# FOLLOWER_DIVIDER.net
KiCad netlist of a schematic drawn in Altium Designer
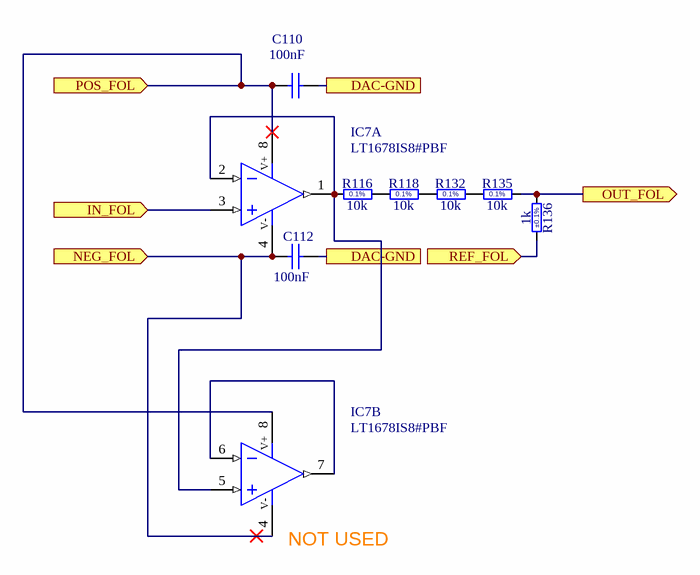
[diagram p0: FOLLOWER_DIVIDER.SchDoc]

(export (version "E")
  (design (tool "Eeschema 10.0.6"))
  (components
    (comp (ref "C110")
      (value "100nF")
      (footprint "CAPC1608X87N")
      (description "Non-polarised capacitor")
      (fields
        (field (name "PART NUMBER") "CC0603_100NF_50V_10%_X7R")
        (field (name "VOLTAGE") "50V")
        (field (name "AUTHOR") "CERN DEM JLC")
      )
      (libsource (lib "Capacitors") (part "Capacitor - non polarized"))
    )
    (comp (ref "C112")
      (value "100nF")
      (footprint "CAPC1608X87N")
      (description "Non-polarised capacitor")
      (fields
        (field (name "PART NUMBER") "CC0603_100NF_50V_10%_X7R")
        (field (name "VOLTAGE") "50V")
        (field (name "AUTHOR") "CERN DEM JLC")
      )
      (libsource (lib "Capacitors") (part "Capacitor - non polarized"))
    )
    (comp (ref "IC7")
      (value "LT1678IS8#PBF")
      (footprint "SOIC127P600X175-8N")
      (description "Dual Operational Amplifier")
      (fields (field (name "MANUFACTURER") "LINEAR TECHNOLOGY") (field (name "AUTHOR") "CERN DEM JLC"))
      (libsource (lib "ICs And Semiconductors") (part "Operational Amplifier x2 Type1"))
    )
    (comp (ref "R116")
      (value "10k")
      (footprint "RESC1608X55N")
      (description "Resistor - 0.1%")
      (fields
        (field (name "PART NUMBER") "R0603_10K_0.1%_0.063W_10PPM")
        (field (name "POWER") "0.063W")
        (field (name "AUTHOR") "CERN DEM JLC")
      )
      (libsource (lib "Resistors") (part "Resistor - 0.1%"))
    )
    (comp (ref "R118")
      (value "10k")
      (footprint "RESC1608X55N")
      (description "Resistor - 0.1%")
      (fields
        (field (name "PART NUMBER") "R0603_10K_0.1%_0.063W_10PPM")
        (field (name "POWER") "0.063W")
        (field (name "AUTHOR") "CERN DEM JLC")
      )
      (libsource (lib "Resistors") (part "Resistor - 0.1%"))
    )
    (comp (ref "R132")
      (value "10k")
      (footprint "RESC1608X55N")
      (description "Resistor - 0.1%")
      (fields
        (field (name "PART NUMBER") "R0603_10K_0.1%_0.063W_10PPM")
        (field (name "POWER") "0.063W")
        (field (name "AUTHOR") "CERN DEM JLC")
      )
      (libsource (lib "Resistors") (part "Resistor - 0.1%"))
    )
    (comp (ref "R135")
      (value "10k")
      (footprint "RESC1608X55N")
      (description "Resistor - 0.1%")
      (fields
        (field (name "PART NUMBER") "R0603_10K_0.1%_0.063W_10PPM")
        (field (name "POWER") "0.063W")
        (field (name "AUTHOR") "CERN DEM JLC")
      )
      (libsource (lib "Resistors") (part "Resistor - 0.1%"))
    )
    (comp (ref "R136")
      (value "1k")
      (footprint "RESC1608X64N")
      (description "Resistor - 0.1%")
      (fields
        (field (name "TOLERANCE") "±0.1%")
        (field (name "PART NUMBER") "R0603_1K_0.1%_0.1W_25PPM")
        (field (name "POWER") "0.1W")
        (field (name "AUTHOR") "CERN DEM JLC")
      )
      (libsource (lib "") (part "Resistor - 0.1%_1"))
    )
  )
  (nets
    (net (code "1") (name "/DAC-GND") (class "Default")
      (node (ref "C110") (pin "2") (pinfunction "2_2") (pintype "passive"))
      (node (ref "C112") (pin "2") (pinfunction "2_2") (pintype "passive"))
    )
    (net (code "2") (name "/IN_FOL") (class "Default")
      (node (ref "IC7") (pin "3") (pinfunction "IN+_3") (pintype "input"))
    )
    (net (code "3") (name "/NEG_FOL") (class "Default")
      (node (ref "C112") (pin "1") (pinfunction "1_1") (pintype "passive"))
      (node (ref "IC7") (pin "4") (pinfunction "V-_4") (pintype "power_in"))
    )
    (net (code "4") (name "/OUT_FOL") (class "Default")
      (node (ref "R135") (pin "2") (pinfunction "2_2") (pintype "passive"))
      (node (ref "R136") (pin "1") (pinfunction "1_1") (pintype "passive"))
    )
    (net (code "5") (name "/POS_FOL") (class "Default")
      (node (ref "C110") (pin "1") (pinfunction "1_1") (pintype "passive"))
      (node (ref "IC7") (pin "8") (pinfunction "V+_8") (pintype "power_in"))
    )
    (net (code "6") (name "/REF_FOL") (class "Default")
      (node (ref "R136") (pin "2") (pinfunction "2_2") (pintype "passive"))
    )
    (net (code "7") (name "Net-(IC7A-IN-)") (class "Default")
      (node (ref "IC7") (pin "1") (pinfunction "OUT_1") (pintype "output"))
      (node (ref "IC7") (pin "2") (pinfunction "IN-_2") (pintype "input"))
      (node (ref "IC7") (pin "5") (pinfunction "IN+_5") (pintype "input"))
      (node (ref "R116") (pin "1") (pinfunction "1_1") (pintype "passive"))
    )
    (net (code "8") (name "Net-(IC7B-IN-)") (class "Default")
      (node (ref "IC7") (pin "6") (pinfunction "IN-_6") (pintype "input"))
      (node (ref "IC7") (pin "7") (pinfunction "OUT_7") (pintype "output"))
    )
    (net (code "9") (name "Net-(R116-Pad2)") (class "Default")
      (node (ref "R116") (pin "2") (pinfunction "2_2") (pintype "passive"))
      (node (ref "R118") (pin "1") (pinfunction "1_1") (pintype "passive"))
    )
    (net (code "10") (name "Net-(R118-Pad2)") (class "Default")
      (node (ref "R118") (pin "2") (pinfunction "2_2") (pintype "passive"))
      (node (ref "R132") (pin "1") (pinfunction "1_1") (pintype "passive"))
    )
    (net (code "11") (name "Net-(R132-Pad2)") (class "Default")
      (node (ref "R132") (pin "2") (pinfunction "2_2") (pintype "passive"))
      (node (ref "R135") (pin "1") (pinfunction "1_1") (pintype "passive"))
    )
  )
)
